# LED-painel.net
KiCad netlist of a schematic drawn in EAGLE
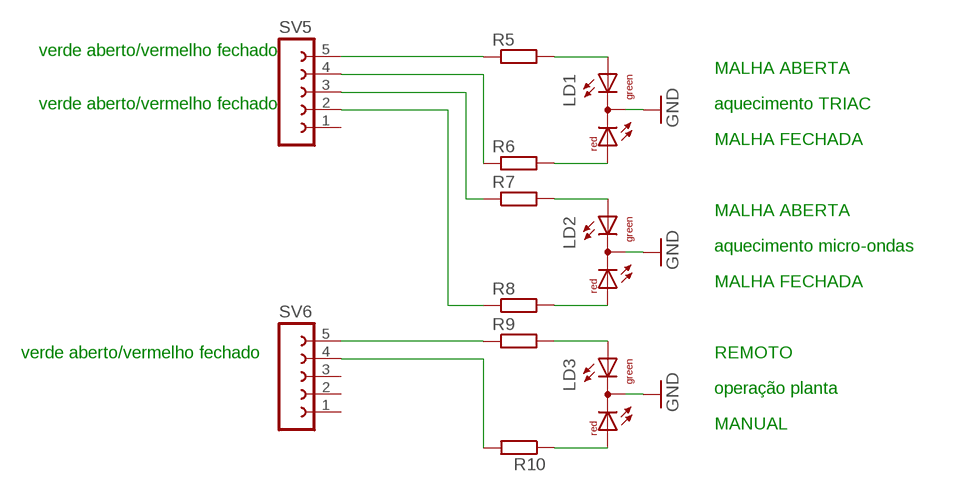
[diagram p0: schematic, sheet 1]

(export (version "E")
  (design (tool "Eeschema 10.0.6"))
  (components
    (comp (ref "LD1")
      (value "DUOLED-RG-C")
      (footprint "eagle-import:DUOLED-C-5MM")
      (libsource (lib "eagle-import") (part "DUOLED-RG-C"))
    )
    (comp (ref "LD2")
      (value "DUOLED-RG-C")
      (footprint "eagle-import:DUOLED-C-5MM")
      (libsource (lib "eagle-import") (part "DUOLED-RG-C"))
    )
    (comp (ref "LD3")
      (value "DUOLED-RG-C")
      (footprint "eagle-import:DUOLED-C-5MM")
      (libsource (lib "eagle-import") (part "DUOLED-RG-C"))
    )
    (comp (ref "R5")
      (value "R-EU_0207/10")
      (footprint "eagle-import:0207_10")
      (libsource (lib "eagle-import") (part "resistor_R-EU_0207/10"))
    )
    (comp (ref "R6")
      (value "R-EU_0207/10")
      (footprint "eagle-import:0207_10")
      (libsource (lib "eagle-import") (part "resistor_R-EU_0207/10"))
    )
    (comp (ref "R7")
      (value "R-EU_0207/10")
      (footprint "eagle-import:0207_10")
      (libsource (lib "eagle-import") (part "resistor_R-EU_0207/10"))
    )
    (comp (ref "R8")
      (value "R-EU_0207/10")
      (footprint "eagle-import:0207_10")
      (libsource (lib "eagle-import") (part "resistor_R-EU_0207/10"))
    )
    (comp (ref "R9")
      (value "R-EU_0207/10")
      (footprint "eagle-import:0207_10")
      (libsource (lib "eagle-import") (part "resistor_R-EU_0207/10"))
    )
    (comp (ref "R10")
      (value "R-EU_0207/10")
      (footprint "eagle-import:0207_10")
      (libsource (lib "eagle-import") (part "R-EU_0207/10"))
    )
    (comp (ref "SV5")
      (value "FE05-1")
      (footprint "eagle-import:FE05-1")
      (libsource (lib "eagle-import") (part "FE05-1"))
    )
    (comp (ref "SV6")
      (value "FE05-1")
      (footprint "eagle-import:FE05-1")
      (libsource (lib "eagle-import") (part "FE05-1"))
    )
  )
  (nets
    (net (code "1") (name "GND") (class "Default")
      (node (ref "LD1") (pin "C") (pinfunction "C_C") (pintype "passive"))
      (node (ref "LD2") (pin "C") (pinfunction "C_C") (pintype "passive"))
      (node (ref "LD3") (pin "C") (pinfunction "C_C") (pintype "passive"))
    )
    (net (code "2") (name "Net-(LD1-AG)") (class "Default")
      (node (ref "LD1") (pin "AX") (pinfunction "AG_AX") (pintype "passive"))
      (node (ref "R5") (pin "2") (pinfunction "2_2") (pintype "passive"))
    )
    (net (code "3") (name "Net-(LD1-PadAR)") (class "Default")
      (node (ref "LD1") (pin "AR") (pinfunction "AR_AR") (pintype "passive"))
      (node (ref "R6") (pin "2") (pinfunction "2_2") (pintype "passive"))
    )
    (net (code "4") (name "Net-(LD2-AG)") (class "Default")
      (node (ref "LD2") (pin "AX") (pinfunction "AG_AX") (pintype "passive"))
      (node (ref "R7") (pin "2") (pinfunction "2_2") (pintype "passive"))
    )
    (net (code "5") (name "Net-(LD2-PadAR)") (class "Default")
      (node (ref "LD2") (pin "AR") (pinfunction "AR_AR") (pintype "passive"))
      (node (ref "R8") (pin "2") (pinfunction "2_2") (pintype "passive"))
    )
    (net (code "6") (name "Net-(LD3-AG)") (class "Default")
      (node (ref "LD3") (pin "AX") (pinfunction "AG_AX") (pintype "passive"))
      (node (ref "R9") (pin "2") (pinfunction "2_2") (pintype "passive"))
    )
    (net (code "7") (name "Net-(LD3-PadAR)") (class "Default")
      (node (ref "LD3") (pin "AR") (pinfunction "AR_AR") (pintype "passive"))
      (node (ref "R10") (pin "1") (pinfunction "1_1") (pintype "passive"))
    )
    (net (code "8") (name "Net-(R5-Pad1)") (class "Default")
      (node (ref "R5") (pin "1") (pinfunction "1_1") (pintype "passive"))
      (node (ref "SV5") (pin "5") (pinfunction "5_5") (pintype "passive"))
    )
    (net (code "9") (name "Net-(R6-Pad1)") (class "Default")
      (node (ref "R6") (pin "1") (pinfunction "1_1") (pintype "passive"))
      (node (ref "SV5") (pin "4") (pinfunction "4_4") (pintype "passive"))
    )
    (net (code "10") (name "Net-(R7-Pad1)") (class "Default")
      (node (ref "R7") (pin "1") (pinfunction "1_1") (pintype "passive"))
      (node (ref "SV5") (pin "3") (pinfunction "3_3") (pintype "passive"))
    )
    (net (code "11") (name "Net-(R8-Pad1)") (class "Default")
      (node (ref "R8") (pin "1") (pinfunction "1_1") (pintype "passive"))
      (node (ref "SV5") (pin "2") (pinfunction "2_2") (pintype "passive"))
    )
    (net (code "12") (name "Net-(R9-Pad1)") (class "Default")
      (node (ref "R9") (pin "1") (pinfunction "1_1") (pintype "passive"))
      (node (ref "SV6") (pin "5") (pinfunction "5_5") (pintype "passive"))
    )
    (net (code "13") (name "Net-(R10-Pad2)") (class "Default")
      (node (ref "R10") (pin "2") (pinfunction "2_2") (pintype "passive"))
      (node (ref "SV6") (pin "4") (pinfunction "4_4") (pintype "passive"))
    )
    (net (code "14") (name "unconnected-(SV5-Pad1)") (class "Default")
      (node (ref "SV5") (pin "1") (pinfunction "1_1") (pintype "passive"))
    )
    (net (code "15") (name "unconnected-(SV6-Pad1)") (class "Default")
      (node (ref "SV6") (pin "1") (pinfunction "1_1") (pintype "passive"))
    )
    (net (code "16") (name "unconnected-(SV6-Pad2)") (class "Default")
      (node (ref "SV6") (pin "2") (pinfunction "2_2") (pintype "passive"))
    )
    (net (code "17") (name "unconnected-(SV6-Pad3)") (class "Default")
      (node (ref "SV6") (pin "3") (pinfunction "3_3") (pintype "passive"))
    )
  )
)
